# FLC100_level_shifting_cloud.net
KiCad netlist of a schematic drawn in EAGLE
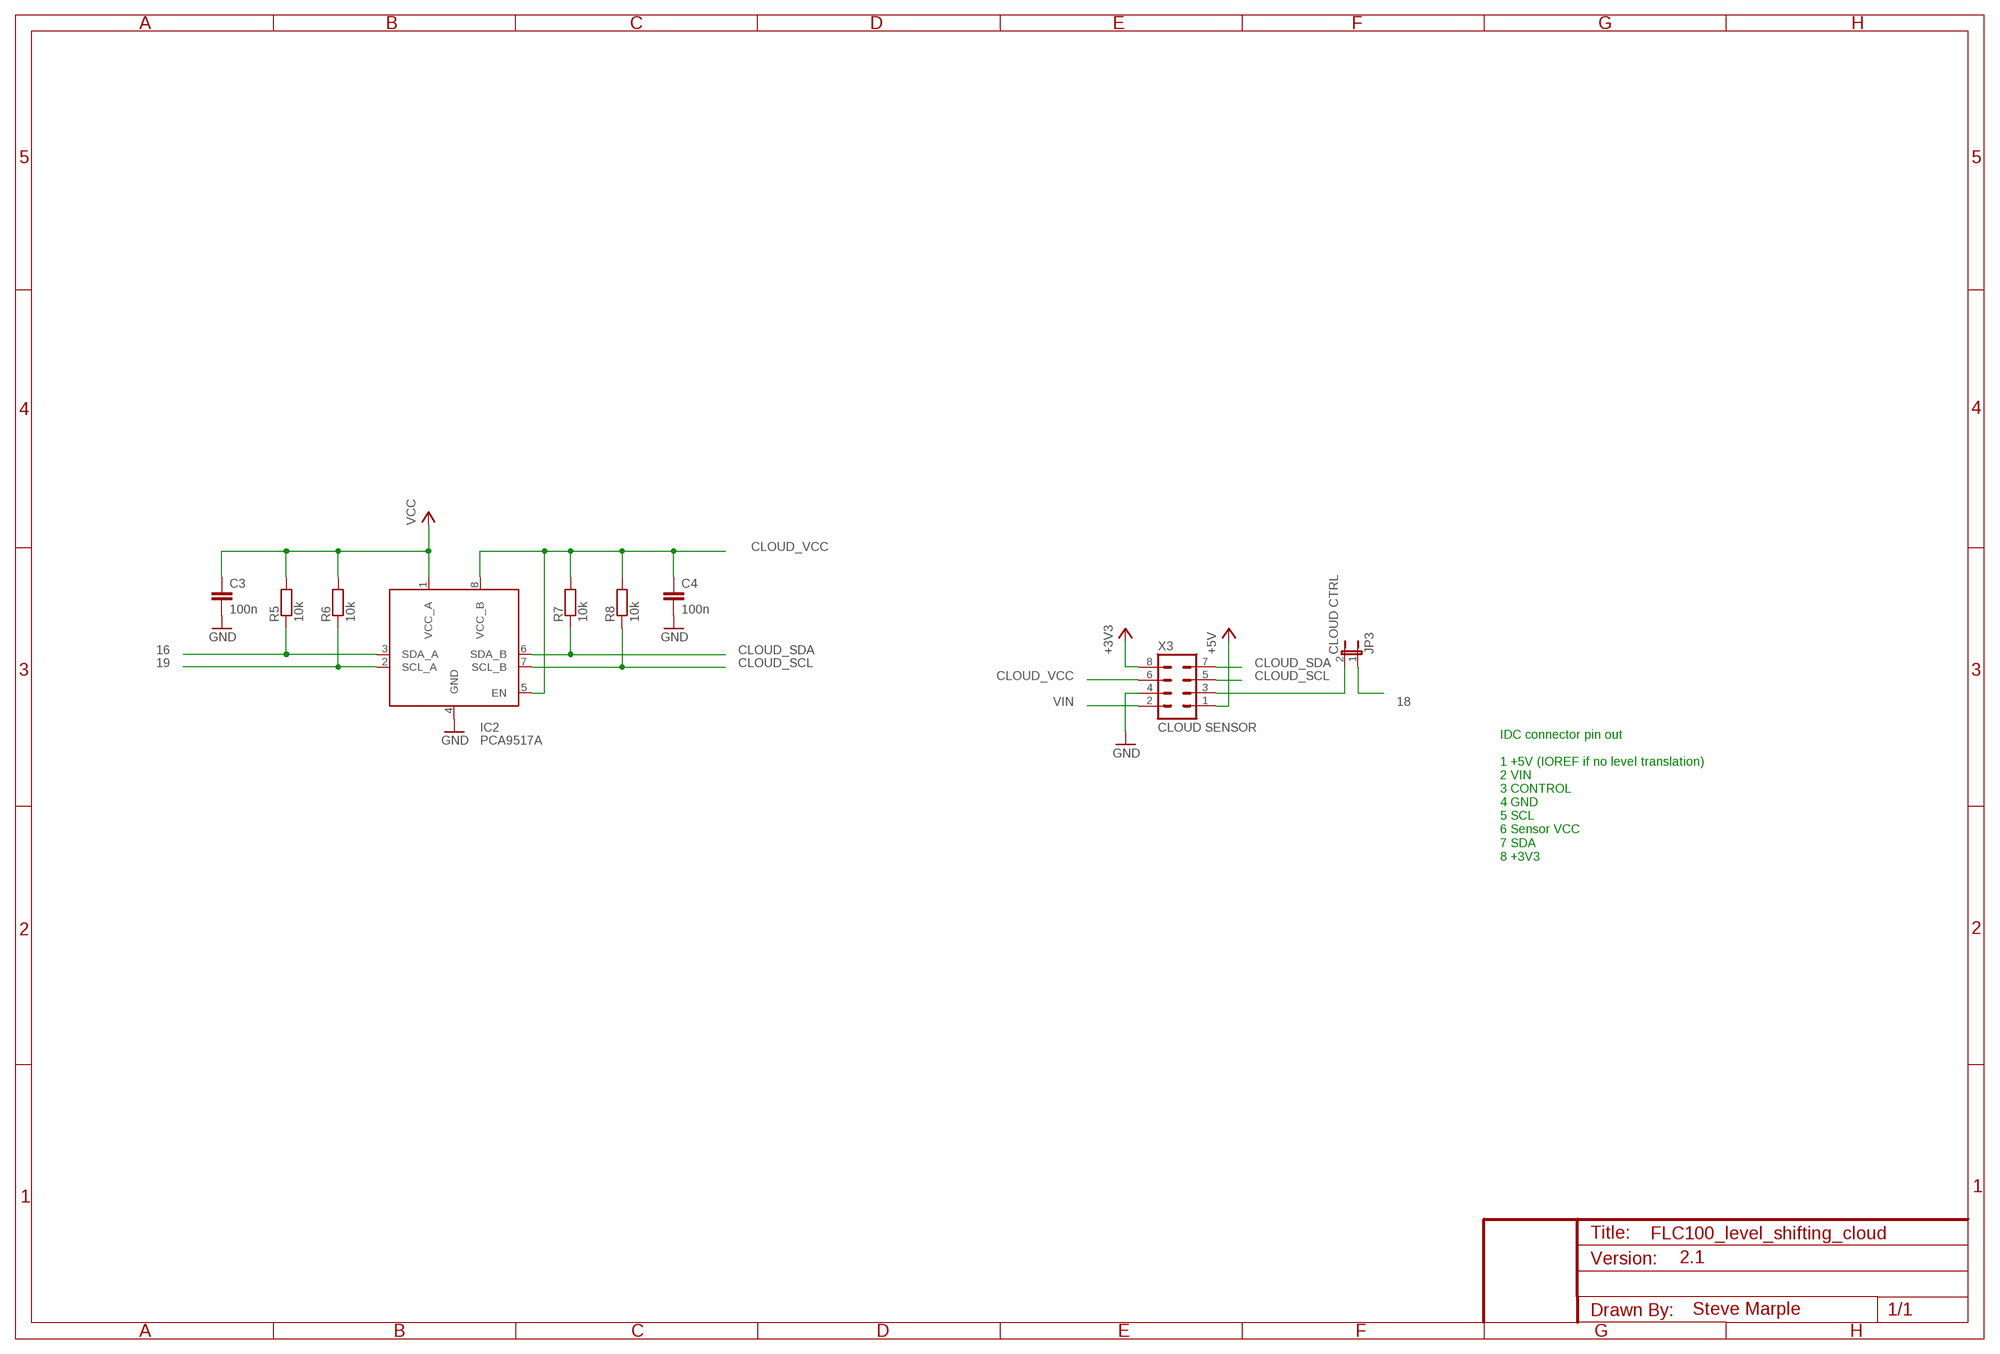
[diagram p0: schematic, sheet 1]

(export (version "E")
  (design (tool "Eeschema 10.0.6"))
  (components
    (comp (ref "C3")
      (value "100n")
      (footprint "eagle-import:1206-HAND")
      (libsource (lib "eagle-import") (part "C-EU1206-HAND"))
    )
    (comp (ref "C4")
      (value "100n")
      (footprint "eagle-import:1206-HAND")
      (libsource (lib "eagle-import") (part "C-EU1206-HAND"))
    )
    (comp (ref "IC2")
      (value "PCA9517A")
      (footprint "eagle-import:SO08")
      (libsource (lib "eagle-import") (part "PCA9517ASOIC"))
    )
    (comp (ref "JP3")
      (value "CLOUD CTRL")
      (footprint "eagle-import:1X02")
      (libsource (lib "eagle-import") (part "JUMPER-2PTH"))
    )
    (comp (ref "R5")
      (value "10k")
      (footprint "eagle-import:1206-HAND")
      (libsource (lib "eagle-import") (part "RESISTOR1206-HAND"))
    )
    (comp (ref "R6")
      (value "10k")
      (footprint "eagle-import:1206-HAND")
      (libsource (lib "eagle-import") (part "RESISTOR1206-HAND"))
    )
    (comp (ref "R7")
      (value "10k")
      (footprint "eagle-import:1206-HAND")
      (libsource (lib "eagle-import") (part "RESISTOR1206-HAND"))
    )
    (comp (ref "R8")
      (value "10k")
      (footprint "eagle-import:1206-HAND")
      (libsource (lib "eagle-import") (part "RESISTOR1206-HAND"))
    )
    (comp (ref "X3")
      (value "CLOUD SENSOR")
      (footprint "eagle-import:ML8")
      (libsource (lib "eagle-import") (part "ML8"))
    )
  )
  (nets
    (net (code "1") (name "+3V3") (class "Default")
      (node (ref "X3") (pin "8") (pinfunction "8_8") (pintype "passive"))
    )
    (net (code "2") (name "+5V") (class "Default")
      (node (ref "X3") (pin "1") (pinfunction "1_1") (pintype "passive"))
    )
    (net (code "3") (name "/16") (class "Default")
      (node (ref "IC2") (pin "3") (pinfunction "SDA_A_3") (pintype "bidirectional"))
      (node (ref "R5") (pin "1") (pinfunction "1_1") (pintype "passive"))
    )
    (net (code "4") (name "/18") (class "Default")
      (node (ref "JP3") (pin "1") (pinfunction "1_1") (pintype "passive"))
    )
    (net (code "5") (name "/19") (class "Default")
      (node (ref "IC2") (pin "2") (pinfunction "SCL_A_2") (pintype "bidirectional"))
      (node (ref "R6") (pin "1") (pinfunction "1_1") (pintype "passive"))
    )
    (net (code "6") (name "/CLOUD_SCL") (class "Default")
      (node (ref "IC2") (pin "7") (pinfunction "SCL_B_7") (pintype "bidirectional"))
      (node (ref "R8") (pin "1") (pinfunction "1_1") (pintype "passive"))
      (node (ref "X3") (pin "5") (pinfunction "5_5") (pintype "passive"))
    )
    (net (code "7") (name "/CLOUD_SDA") (class "Default")
      (node (ref "IC2") (pin "6") (pinfunction "SDA_B_6") (pintype "bidirectional"))
      (node (ref "R7") (pin "1") (pinfunction "1_1") (pintype "passive"))
      (node (ref "X3") (pin "7") (pinfunction "7_7") (pintype "passive"))
    )
    (net (code "8") (name "/CLOUD_VCC") (class "Default")
      (node (ref "C4") (pin "1") (pinfunction "1_1") (pintype "passive"))
      (node (ref "IC2") (pin "5") (pinfunction "EN_5") (pintype "bidirectional"))
      (node (ref "IC2") (pin "8") (pinfunction "VCC_B_8") (pintype "power_in"))
      (node (ref "R7") (pin "2") (pinfunction "2_2") (pintype "passive"))
      (node (ref "R8") (pin "2") (pinfunction "2_2") (pintype "passive"))
      (node (ref "X3") (pin "6") (pinfunction "6_6") (pintype "passive"))
    )
    (net (code "9") (name "/VIN") (class "Default")
      (node (ref "X3") (pin "2") (pinfunction "2_2") (pintype "passive"))
    )
    (net (code "10") (name "GND") (class "Default")
      (node (ref "C3") (pin "2") (pinfunction "2_2") (pintype "passive"))
      (node (ref "C4") (pin "2") (pinfunction "2_2") (pintype "passive"))
      (node (ref "IC2") (pin "4") (pinfunction "GND_4") (pintype "power_in"))
      (node (ref "X3") (pin "4") (pinfunction "4_4") (pintype "passive"))
    )
    (net (code "11") (name "Net-(JP3-Pad2)") (class "Default")
      (node (ref "JP3") (pin "2") (pinfunction "2_2") (pintype "passive"))
      (node (ref "X3") (pin "3") (pinfunction "3_3") (pintype "passive"))
    )
    (net (code "12") (name "VCC") (class "Default")
      (node (ref "C3") (pin "1") (pinfunction "1_1") (pintype "passive"))
      (node (ref "IC2") (pin "1") (pinfunction "VCC_A_1") (pintype "power_in"))
      (node (ref "R5") (pin "2") (pinfunction "2_2") (pintype "passive"))
      (node (ref "R6") (pin "2") (pinfunction "2_2") (pintype "passive"))
    )
  )
)
